# TM1638_on_ATtiny841.net
KiCad netlist of a schematic drawn in EAGLE
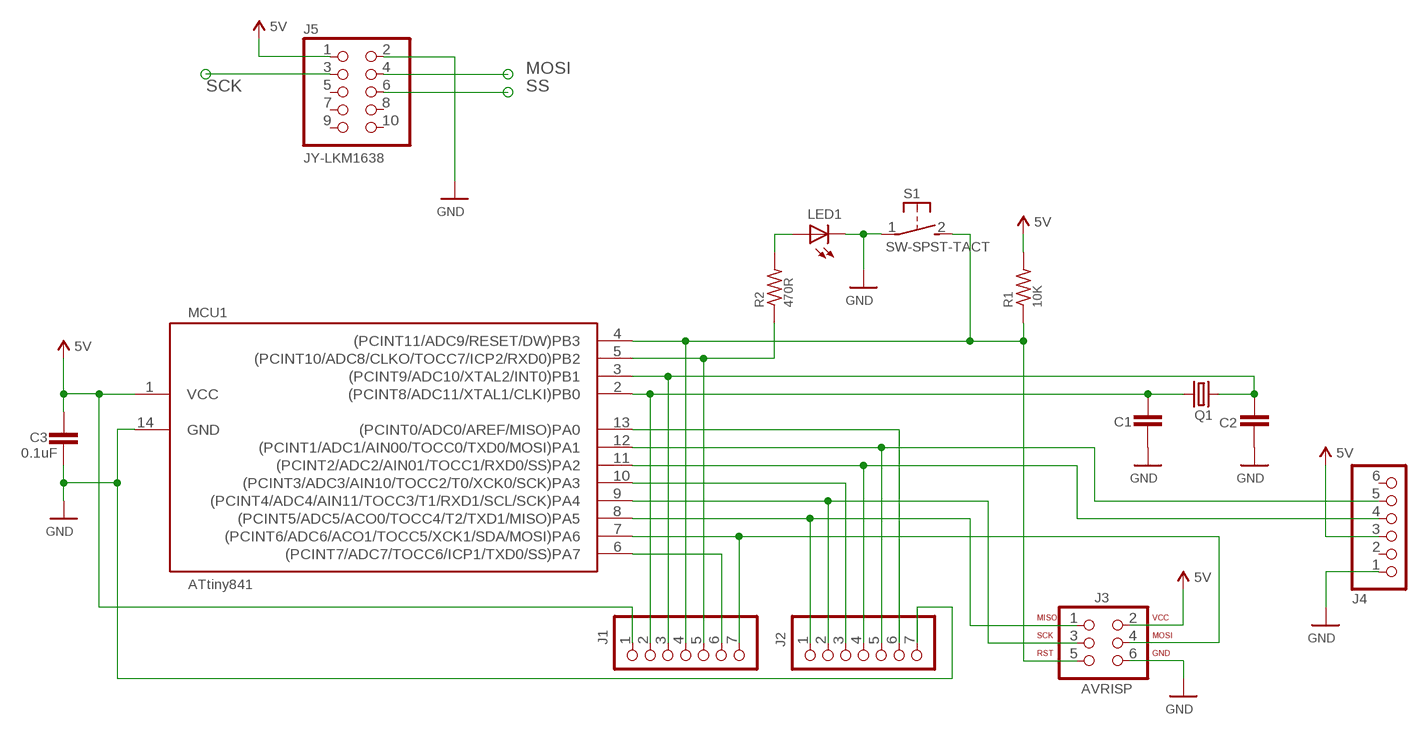
[diagram p0: schematic, sheet 1]

(export (version "E")
  (design (tool "Eeschema 10.0.6"))
  (components
    (comp (ref "C1")
      (value "C-UNPOL")
      (footprint "eagle-import:CAP-PTH-SMALL2")
      (libsource (lib "eagle-import") (part "C-UNPOL"))
    )
    (comp (ref "C2")
      (value "C-UNPOL")
      (footprint "eagle-import:CAP-PTH-SMALL2")
      (libsource (lib "eagle-import") (part "C-UNPOL"))
    )
    (comp (ref "C3")
      (value "0.1uF")
      (footprint "eagle-import:CAP-PTH-SMALL2")
      (libsource (lib "eagle-import") (part "C-UNPOL"))
    )
    (comp (ref "J1")
      (value "PINHD-1X71X07-CLEANBIG")
      (footprint "eagle-import:1X07-CLEANBIG")
      (libsource (lib "eagle-import") (part "PINHD-1X71X07-CLEANBIG"))
    )
    (comp (ref "J2")
      (value "PINHD-1X71X07-CLEANBIG")
      (footprint "eagle-import:1X07-CLEANBIG")
      (libsource (lib "eagle-import") (part "PINHD-1X71X07-CLEANBIG"))
    )
    (comp (ref "J3")
      (value "AVRISP")
      (footprint "eagle-import:2X03-CLEAN")
      (libsource (lib "eagle-import") (part "AVRISP"))
    )
    (comp (ref "J4")
      (value "PINHD-1X6CB")
      (footprint "eagle-import:1X06-CLEANBIG")
      (libsource (lib "eagle-import") (part "PINHD-1X6CB"))
    )
    (comp (ref "J5")
      (value "JY-LKM1638")
      (footprint "eagle-import:2X05")
      (libsource (lib "eagle-import") (part "PINHD-2X5"))
    )
    (comp (ref "LED1")
      (value "LED5MM")
      (footprint "eagle-import:LED5MM")
      (libsource (lib "eagle-import") (part "LED5MM"))
    )
    (comp (ref "MCU1")
      (value "ATtiny841")
      (footprint "eagle-import:SOIC14")
      (libsource (lib "eagle-import") (part "ATTINY441/841-SSU"))
    )
    (comp (ref "Q1")
      (value "CRYSTALHC49S")
      (footprint "eagle-import:HC49_S")
      (libsource (lib "eagle-import") (part "CRYSTALHC49S"))
    )
    (comp (ref "R1")
      (value "10K")
      (footprint "eagle-import:RESISTOR-0207_2V")
      (libsource (lib "eagle-import") (part "RESISTOR-0207/V"))
    )
    (comp (ref "R2")
      (value "470R")
      (footprint "eagle-import:RESISTOR-0207_2V")
      (libsource (lib "eagle-import") (part "RESISTOR-0207/V"))
    )
    (comp (ref "S1")
      (value "SW-SPST-TACT")
      (footprint "eagle-import:DTS-3")
      (libsource (lib "eagle-import") (part "SW-SPST-TACT"))
    )
  )
  (nets
    (net (code "1") (name "/MOSI") (class "Default")
      (node (ref "J1") (pin "7") (pinfunction "7_7") (pintype "passive"))
      (node (ref "J3") (pin "4") (pinfunction "4_4") (pintype "passive"))
      (node (ref "J5") (pin "4") (pinfunction "4_4") (pintype "passive"))
      (node (ref "MCU1") (pin "7") (pinfunction "(PCINT6/ADC6/ACO1/TOCC5/XCK1/SDA/MOSI)PA6_7") (pintype "bidirectional"))
    )
    (net (code "2") (name "/SCK") (class "Default")
      (node (ref "J2") (pin "2") (pinfunction "2_2") (pintype "passive"))
      (node (ref "J3") (pin "3") (pinfunction "3_3") (pintype "passive"))
      (node (ref "J5") (pin "3") (pinfunction "3_3") (pintype "passive"))
      (node (ref "MCU1") (pin "9") (pinfunction "(PCINT4/ADC4/AIN11/TOCC3/T1/RXD1/SCL/SCK)PA4_9") (pintype "bidirectional"))
    )
    (net (code "3") (name "/SS") (class "Default")
      (node (ref "J1") (pin "6") (pinfunction "6_6") (pintype "passive"))
      (node (ref "J5") (pin "6") (pinfunction "6_6") (pintype "passive"))
      (node (ref "MCU1") (pin "6") (pinfunction "(PCINT7/ADC7/TOCC6/ICP1/TXD0/SS)PA7_6") (pintype "bidirectional"))
    )
    (net (code "4") (name "5V") (class "Default")
      (node (ref "C3") (pin "1") (pinfunction "1_1") (pintype "passive"))
      (node (ref "J1") (pin "1") (pinfunction "1_1") (pintype "passive"))
      (node (ref "J3") (pin "2") (pinfunction "2_2") (pintype "passive"))
      (node (ref "J4") (pin "3") (pinfunction "3_3") (pintype "passive"))
      (node (ref "J5") (pin "1") (pinfunction "1_1") (pintype "passive"))
      (node (ref "MCU1") (pin "1") (pinfunction "VCC_1") (pintype "bidirectional"))
      (node (ref "R1") (pin "2") (pinfunction "2_2") (pintype "passive"))
    )
    (net (code "5") (name "GND") (class "Default")
      (node (ref "C1") (pin "2") (pinfunction "2_2") (pintype "passive"))
      (node (ref "C2") (pin "1") (pinfunction "1_1") (pintype "passive"))
      (node (ref "C3") (pin "2") (pinfunction "2_2") (pintype "passive"))
      (node (ref "J2") (pin "7") (pinfunction "7_7") (pintype "passive"))
      (node (ref "J3") (pin "6") (pinfunction "6_6") (pintype "passive"))
      (node (ref "J4") (pin "1") (pinfunction "1_1") (pintype "passive"))
      (node (ref "J5") (pin "2") (pinfunction "2_2") (pintype "passive"))
      (node (ref "LED1") (pin "K") (pinfunction "C_K") (pintype "passive"))
      (node (ref "MCU1") (pin "14") (pinfunction "GND_14") (pintype "bidirectional"))
      (node (ref "S1") (pin "1") (pinfunction "1_1") (pintype "passive"))
    )
    (net (code "6") (name "Net-(LED1-PadA)") (class "Default")
      (node (ref "LED1") (pin "A") (pinfunction "A_A") (pintype "passive"))
      (node (ref "R2") (pin "2") (pinfunction "2_2") (pintype "passive"))
    )
    (net (code "7") (name "Net-(MCU1-(PCINT0{slash}ADC0{slash}AREF{slash}MISO)PA0)") (class "Default")
      (node (ref "J2") (pin "6") (pinfunction "6_6") (pintype "passive"))
      (node (ref "MCU1") (pin "13") (pinfunction "(PCINT0/ADC0/AREF/MISO)PA0_13") (pintype "bidirectional"))
    )
    (net (code "8") (name "Net-(MCU1-(PCINT1{slash}ADC1{slash}AIN00{slash}TOCC0{slash}TXD0{slash}MOSI)PA1)") (class "Default")
      (node (ref "J2") (pin "5") (pinfunction "5_5") (pintype "passive"))
      (node (ref "J4") (pin "5") (pinfunction "5_5") (pintype "passive"))
      (node (ref "MCU1") (pin "12") (pinfunction "(PCINT1/ADC1/AIN00/TOCC0/TXD0/MOSI)PA1_12") (pintype "bidirectional"))
    )
    (net (code "9") (name "Net-(MCU1-(PCINT2{slash}ADC2{slash}AIN01{slash}TOCC1{slash}RXD0{slash}SS)PA2)") (class "Default")
      (node (ref "J2") (pin "4") (pinfunction "4_4") (pintype "passive"))
      (node (ref "J4") (pin "4") (pinfunction "4_4") (pintype "passive"))
      (node (ref "MCU1") (pin "11") (pinfunction "(PCINT2/ADC2/AIN01/TOCC1/RXD0/SS)PA2_11") (pintype "bidirectional"))
    )
    (net (code "10") (name "Net-(MCU1-(PCINT3{slash}ADC3{slash}AIN10{slash}TOCC2{slash}T0{slash}XCK0{slash}SCK)PA3)") (class "Default")
      (node (ref "J2") (pin "3") (pinfunction "3_3") (pintype "passive"))
      (node (ref "MCU1") (pin "10") (pinfunction "(PCINT3/ADC3/AIN10/TOCC2/T0/XCK0/SCK)PA3_10") (pintype "bidirectional"))
    )
    (net (code "11") (name "Net-(MCU1-(PCINT5{slash}ADC5{slash}ACO0{slash}TOCC4{slash}T2{slash}TXD1{slash}MISO)PA5)") (class "Default")
      (node (ref "J2") (pin "1") (pinfunction "1_1") (pintype "passive"))
      (node (ref "J3") (pin "1") (pinfunction "1_1") (pintype "passive"))
      (node (ref "MCU1") (pin "8") (pinfunction "(PCINT5/ADC5/ACO0/TOCC4/T2/TXD1/MISO)PA5_8") (pintype "bidirectional"))
    )
    (net (code "12") (name "Net-(MCU1-(PCINT8{slash}ADC11{slash}XTAL1{slash}CLKI)PB0)") (class "Default")
      (node (ref "C1") (pin "1") (pinfunction "1_1") (pintype "passive"))
      (node (ref "J1") (pin "2") (pinfunction "2_2") (pintype "passive"))
      (node (ref "MCU1") (pin "2") (pinfunction "(PCINT8/ADC11/XTAL1/CLKI)PB0_2") (pintype "bidirectional"))
      (node (ref "Q1") (pin "1") (pinfunction "1_1") (pintype "passive"))
    )
    (net (code "13") (name "Net-(MCU1-(PCINT9{slash}ADC10{slash}XTAL2{slash}INT0)PB1)") (class "Default")
      (node (ref "C2") (pin "2") (pinfunction "2_2") (pintype "passive"))
      (node (ref "J1") (pin "3") (pinfunction "3_3") (pintype "passive"))
      (node (ref "MCU1") (pin "3") (pinfunction "(PCINT9/ADC10/XTAL2/INT0)PB1_3") (pintype "bidirectional"))
      (node (ref "Q1") (pin "2") (pinfunction "2_2") (pintype "passive"))
    )
    (net (code "14") (name "Net-(MCU1-(PCINT10{slash}ADC8{slash}CLKO{slash}TOCC7{slash}ICP2{slash}RXD0)PB2)") (class "Default")
      (node (ref "J1") (pin "5") (pinfunction "5_5") (pintype "passive"))
      (node (ref "MCU1") (pin "5") (pinfunction "(PCINT10/ADC8/CLKO/TOCC7/ICP2/RXD0)PB2_5") (pintype "bidirectional"))
      (node (ref "R2") (pin "1") (pinfunction "1_1") (pintype "passive"))
    )
    (net (code "15") (name "Net-(MCU1-(PCINT11{slash}ADC9{slash}RESET{slash}DW)PB3)") (class "Default")
      (node (ref "J1") (pin "4") (pinfunction "4_4") (pintype "passive"))
      (node (ref "J3") (pin "5") (pinfunction "5_5") (pintype "passive"))
      (node (ref "MCU1") (pin "4") (pinfunction "(PCINT11/ADC9/RESET/DW)PB3_4") (pintype "bidirectional"))
      (node (ref "R1") (pin "1") (pinfunction "1_1") (pintype "passive"))
      (node (ref "S1") (pin "2") (pinfunction "2_2") (pintype "passive"))
    )
    (net (code "16") (name "unconnected-(J4-Pad2)") (class "Default")
      (node (ref "J4") (pin "2") (pinfunction "2_2") (pintype "passive"))
    )
    (net (code "17") (name "unconnected-(J4-Pad6)") (class "Default")
      (node (ref "J4") (pin "6") (pinfunction "6_6") (pintype "passive"))
    )
    (net (code "18") (name "unconnected-(J5-Pad5)") (class "Default")
      (node (ref "J5") (pin "5") (pinfunction "5_5") (pintype "passive"))
    )
    (net (code "19") (name "unconnected-(J5-Pad7)") (class "Default")
      (node (ref "J5") (pin "7") (pinfunction "7_7") (pintype "passive"))
    )
    (net (code "20") (name "unconnected-(J5-Pad8)") (class "Default")
      (node (ref "J5") (pin "8") (pinfunction "8_8") (pintype "passive"))
    )
    (net (code "21") (name "unconnected-(J5-Pad9)") (class "Default")
      (node (ref "J5") (pin "9") (pinfunction "9_9") (pintype "passive"))
    )
    (net (code "22") (name "unconnected-(J5-Pad10)") (class "Default")
      (node (ref "J5") (pin "10") (pinfunction "10_10") (pintype "passive"))
    )
  )
)
